# LM386.net
KiCad netlist of a schematic drawn in Altium Designer
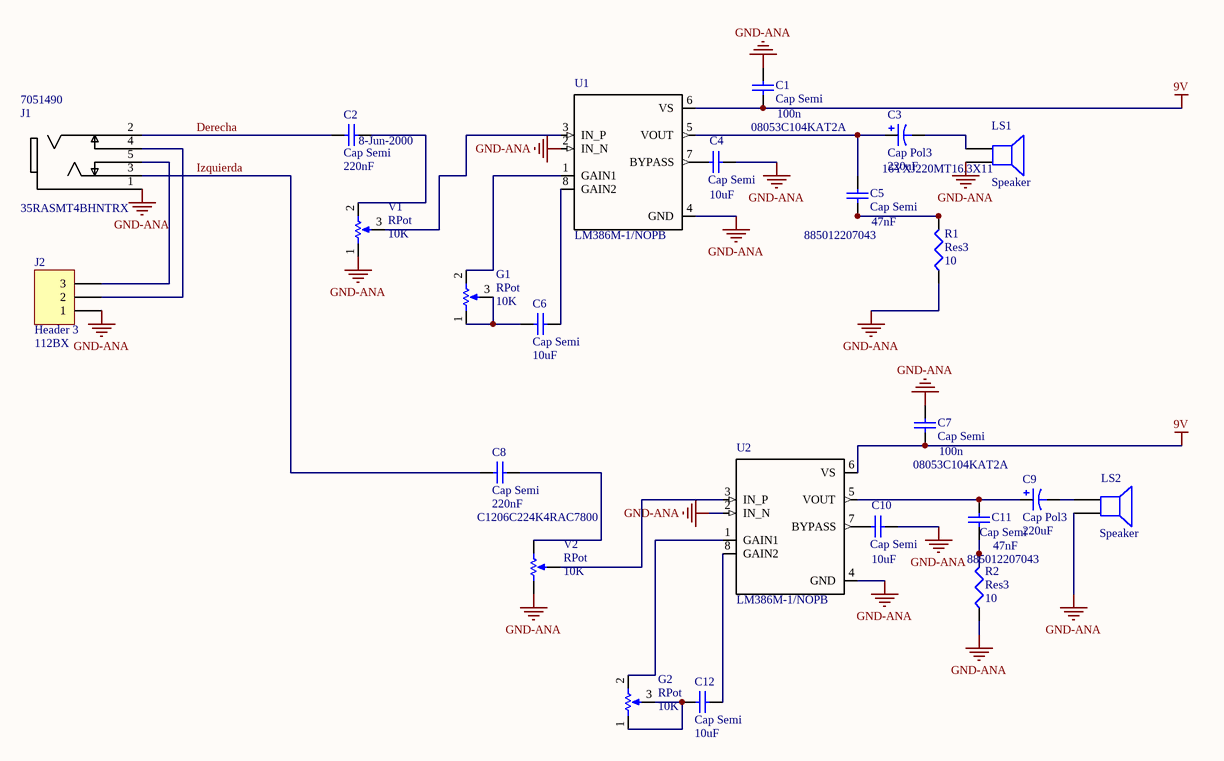
[diagram p0: LM386.SchDoc]

(export (version "E")
  (design (tool "Eeschema 10.0.6"))
  (components
    (comp (ref "C1")
      (value "Cap Semi")
      (footprint "C0805")
      (description "Capacitor (Semiconductor SIM Model)")
      (fields
        (field (name "ALTIUM_VALUE") "100n")
        (field (name "PN") "08053C104KAT2A")
        (field (name "PUBLISHER") "Altium Limited")
      )
      (libsource (lib "Miscellaneous Devices") (part "Cap Semi"))
    )
    (comp (ref "C2")
      (value "Cap Semi")
      (footprint "C1206")
      (description "Capacitor (Semiconductor SIM Model)")
      (fields
        (field (name "PUBLISHED") "8-Jun-2000")
        (field (name "ALTIUM_VALUE") "220nF")
        (field (name "PUBLISHER") "Altium Limited")
      )
      (libsource (lib "Miscellaneous Devices") (part "Cap Semi"))
    )
    (comp (ref "C3")
      (value "Cap Pol3")
      (footprint "C0805")
      (description "Polarized Capacitor (Surface Mount)")
      (fields
        (field (name "ALTIUM_VALUE") "220uF")
        (field (name "PN") "16YXJ220MT16.3X11")
        (field (name "PUBLISHER") "Altium Limited")
      )
      (libsource (lib "Miscellaneous Devices") (part "Cap Pol3"))
    )
    (comp (ref "C4")
      (value "Cap Semi")
      (footprint "C1206")
      (description "Capacitor (Semiconductor SIM Model)")
      (fields (field (name "ALTIUM_VALUE") "10uF") (field (name "PUBLISHER") "Altium Limited"))
      (libsource (lib "Miscellaneous Devices") (part "Cap Semi"))
    )
    (comp (ref "C5")
      (value "Cap Semi")
      (footprint "C0805")
      (description "Capacitor (Semiconductor SIM Model)")
      (fields
        (field (name "ALTIUM_VALUE") "47nF")
        (field (name "PN") "885012207043")
        (field (name "PUBLISHER") "Altium Limited")
      )
      (libsource (lib "Miscellaneous Devices") (part "Cap Semi"))
    )
    (comp (ref "C6")
      (value "Cap Semi")
      (footprint "C0805")
      (description "Capacitor (Semiconductor SIM Model)")
      (fields (field (name "ALTIUM_VALUE") "10uF") (field (name "PUBLISHER") "Altium Limited"))
      (libsource (lib "Miscellaneous Devices") (part "Cap Semi"))
    )
    (comp (ref "C7")
      (value "Cap Semi")
      (footprint "C0805")
      (description "Capacitor (Semiconductor SIM Model)")
      (fields
        (field (name "ALTIUM_VALUE") "100n")
        (field (name "PN") "08053C104KAT2A")
        (field (name "PUBLISHER") "Altium Limited")
      )
      (libsource (lib "Miscellaneous Devices") (part "Cap Semi"))
    )
    (comp (ref "C8")
      (value "Cap Semi")
      (footprint "C1206")
      (description "Capacitor (Semiconductor SIM Model)")
      (fields
        (field (name "ALTIUM_VALUE") "220nF")
        (field (name "PN") "C1206C224K4RAC7800")
        (field (name "PUBLISHER") "Altium Limited")
      )
      (libsource (lib "Miscellaneous Devices") (part "Cap Semi"))
    )
    (comp (ref "C9")
      (value "Cap Pol3")
      (footprint "C0805")
      (description "Polarized Capacitor (Surface Mount)")
      (fields (field (name "ALTIUM_VALUE") "220uF") (field (name "PUBLISHER") "Altium Limited"))
      (libsource (lib "Miscellaneous Devices") (part "Cap Pol3"))
    )
    (comp (ref "C10")
      (value "Cap Semi")
      (footprint "C0805")
      (description "Capacitor (Semiconductor SIM Model)")
      (fields (field (name "ALTIUM_VALUE") "10uF") (field (name "PUBLISHER") "Altium Limited"))
      (libsource (lib "Miscellaneous Devices") (part "Cap Semi"))
    )
    (comp (ref "C11")
      (value "Cap Semi")
      (footprint "C0805")
      (description "Capacitor (Semiconductor SIM Model)")
      (fields
        (field (name "ALTIUM_VALUE") "47nF")
        (field (name "PN") "885012207043")
        (field (name "PUBLISHER") "Altium Limited")
      )
      (libsource (lib "Miscellaneous Devices") (part "Cap Semi"))
    )
    (comp (ref "C12")
      (value "Cap Semi")
      (footprint "C0805")
      (description "Capacitor (Semiconductor SIM Model)")
      (fields (field (name "ALTIUM_VALUE") "10uF") (field (name "PUBLISHER") "Altium Limited"))
      (libsource (lib "Miscellaneous Devices") (part "Cap Semi"))
    )
    (comp (ref "G1")
      (value "RPot")
      (footprint "Potenciometer")
      (description "Potentiometer")
      (fields (field (name "ALTIUM_VALUE") "10K") (field (name "PUBLISHER") "Altium Limited"))
      (libsource (lib "Miscellaneous Devices") (part "RPot"))
    )
    (comp (ref "G2")
      (value "RPot")
      (footprint "Potenciometer")
      (description "Potentiometer")
      (fields (field (name "ALTIUM_VALUE") "10K") (field (name "PUBLISHER") "Altium Limited"))
      (libsource (lib "Miscellaneous Devices") (part "RPot"))
    )
    (comp (ref "J1")
      (value "35RASMT4BHNTRX")
      (footprint "SWITCHCRAFT_35RASMT4BHNTRX")
      (description "Conn 3.5MM Stereo Jack F 3 POS Solder RA SMD 5 Terminal 1 Port T/R")
      (fields (field (name "MF") "Switchcraft") (field (name "SUPPLIER PART NUMBER 1") "7051490"))
      (libsource (lib "35RASMT4BHNTRX") (part "35RASMT4BHNTRX"))
    )
    (comp (ref "J2")
      (value "Header 3")
      (footprint "HDR1X3")
      (description "Header, 3-Pin")
      (fields (field (name "PN") "112BX") (field (name "PUBLISHER") "Altium Limited"))
      (libsource (lib "Miscellaneous Connectors") (part "Header 3"))
    )
    (comp (ref "LS1")
      (value "Speaker")
      (footprint "PIN2")
      (description "Loudspeaker")
      (fields (field (name "PUBLISHER") "Altium Limited"))
      (libsource (lib "Miscellaneous Devices") (part "Speaker"))
    )
    (comp (ref "LS2")
      (value "Speaker")
      (footprint "PIN2")
      (description "Loudspeaker")
      (fields (field (name "PUBLISHER") "Altium Limited"))
      (libsource (lib "Miscellaneous Devices") (part "Speaker"))
    )
    (comp (ref "R1")
      (value "Res3")
      (footprint "SMD-0805-RES")
      (description "Resistor")
      (fields (field (name "ALTIUM_VALUE") "10") (field (name "PUBLISHER") "Altium Limited"))
      (libsource (lib "Miscellaneous Devices") (part "Res3"))
    )
    (comp (ref "R2")
      (value "Res3")
      (footprint "SMD-0805-RES")
      (description "Resistor")
      (fields (field (name "ALTIUM_VALUE") "10") (field (name "PUBLISHER") "Altium Limited"))
      (libsource (lib "Miscellaneous Devices") (part "Res3"))
    )
    (comp (ref "U1")
      (value "LM386M-1/NOPB")
      (footprint "SOIC127P600X175-8N")
      (description "Wide Input Voltage Low Power Audio Amplifier with Internal Gain 8-SOIC 0 to 70")
      (fields (field (name "MF") "Texas Instruments"))
      (libsource (lib "LM386M-1_NOPB") (part "LM386M-1/NOPB"))
    )
    (comp (ref "U2")
      (value "LM386M-1/NOPB")
      (footprint "SOIC127P600X175-8N")
      (description "Wide Input Voltage Low Power Audio Amplifier with Internal Gain 8-SOIC 0 to 70")
      (fields (field (name "MF") "Texas Instruments"))
      (libsource (lib "LM386M-1_NOPB") (part "LM386M-1/NOPB"))
    )
    (comp (ref "V1")
      (value "RPot")
      (footprint "Potenciometer")
      (description "Potentiometer")
      (fields (field (name "ALTIUM_VALUE") "10K") (field (name "PUBLISHER") "Altium Limited"))
      (libsource (lib "Miscellaneous Devices") (part "RPot"))
    )
    (comp (ref "V2")
      (value "RPot")
      (footprint "Potenciometer")
      (description "Potentiometer")
      (fields (field (name "ALTIUM_VALUE") "10K") (field (name "PUBLISHER") "Altium Limited"))
      (libsource (lib "") (part "RPot_1"))
    )
  )
  (nets
    (net (code "1") (name "/Derecha") (class "Default")
      (node (ref "C2") (pin "2") (pinfunction "2_2") (pintype "passive"))
      (node (ref "J1") (pin "2") (pinfunction "2_2") (pintype "passive"))
    )
    (net (code "2") (name "/Izquierda") (class "Default")
      (node (ref "C8") (pin "2") (pinfunction "2_2") (pintype "passive"))
      (node (ref "J1") (pin "3") (pinfunction "3_3") (pintype "passive"))
    )
    (net (code "3") (name "9V") (class "Default")
      (node (ref "C1") (pin "2") (pinfunction "2_2") (pintype "passive"))
      (node (ref "C7") (pin "2") (pinfunction "2_2") (pintype "passive"))
      (node (ref "U1") (pin "6") (pinfunction "VS_6") (pintype "power_in"))
      (node (ref "U2") (pin "6") (pinfunction "VS_6") (pintype "power_in"))
    )
    (net (code "4") (name "GND-ANA") (class "Default")
      (node (ref "C1") (pin "1") (pinfunction "1_1") (pintype "passive"))
      (node (ref "C10") (pin "1") (pinfunction "1_1") (pintype "passive"))
      (node (ref "C4") (pin "1") (pinfunction "1_1") (pintype "passive"))
      (node (ref "C7") (pin "1") (pinfunction "1_1") (pintype "passive"))
      (node (ref "J1") (pin "1") (pinfunction "1_1") (pintype "passive"))
      (node (ref "J2") (pin "1") (pinfunction "1_1") (pintype "passive"))
      (node (ref "LS1") (pin "2") (pinfunction "2_2") (pintype "passive"))
      (node (ref "LS2") (pin "2") (pinfunction "2_2") (pintype "passive"))
      (node (ref "R1") (pin "1") (pinfunction "1_1") (pintype "passive"))
      (node (ref "R2") (pin "1") (pinfunction "1_1") (pintype "passive"))
      (node (ref "U1") (pin "2") (pinfunction "IN_N_2") (pintype "input"))
      (node (ref "U1") (pin "4") (pinfunction "GND_4") (pintype "power_in"))
      (node (ref "U2") (pin "2") (pinfunction "IN_N_2") (pintype "input"))
      (node (ref "U2") (pin "4") (pinfunction "GND_4") (pintype "power_in"))
      (node (ref "V1") (pin "1") (pinfunction "TOP_1") (pintype "passive"))
      (node (ref "V2") (pin "1") (pinfunction "TOP_1") (pintype "passive"))
    )
    (net (code "5") (name "Net-(C3-Pad2)") (class "Default")
      (node (ref "C3") (pin "2") (pinfunction "2_2") (pintype "passive"))
      (node (ref "LS1") (pin "1") (pinfunction "1_1") (pintype "passive"))
    )
    (net (code "6") (name "Net-(C5-Pad2)") (class "Default")
      (node (ref "C5") (pin "2") (pinfunction "2_2") (pintype "passive"))
      (node (ref "R1") (pin "2") (pinfunction "2_2") (pintype "passive"))
    )
    (net (code "7") (name "Net-(C9-Pad2)") (class "Default")
      (node (ref "C9") (pin "2") (pinfunction "2_2") (pintype "passive"))
      (node (ref "LS2") (pin "1") (pinfunction "1_1") (pintype "passive"))
    )
    (net (code "8") (name "Net-(C11-Pad2)") (class "Default")
      (node (ref "C11") (pin "2") (pinfunction "2_2") (pintype "passive"))
      (node (ref "R2") (pin "2") (pinfunction "2_2") (pintype "passive"))
    )
    (net (code "9") (name "Net-(G1-BOT)") (class "Default")
      (node (ref "G1") (pin "2") (pinfunction "BOT_2") (pintype "passive"))
      (node (ref "U1") (pin "1") (pinfunction "GAIN1_1") (pintype "passive"))
    )
    (net (code "10") (name "Net-(G1-TAP)") (class "Default")
      (node (ref "C6") (pin "2") (pinfunction "2_2") (pintype "passive"))
      (node (ref "G1") (pin "1") (pinfunction "TOP_1") (pintype "passive"))
      (node (ref "G1") (pin "3") (pinfunction "TAP_3") (pintype "passive"))
    )
    (net (code "11") (name "Net-(G2-BOT)") (class "Default")
      (node (ref "G2") (pin "2") (pinfunction "BOT_2") (pintype "passive"))
      (node (ref "U2") (pin "1") (pinfunction "GAIN1_1") (pintype "passive"))
    )
    (net (code "12") (name "Net-(G2-TAP)") (class "Default")
      (node (ref "C12") (pin "2") (pinfunction "2_2") (pintype "passive"))
      (node (ref "G2") (pin "1") (pinfunction "TOP_1") (pintype "passive"))
      (node (ref "G2") (pin "3") (pinfunction "TAP_3") (pintype "passive"))
    )
    (net (code "13") (name "Net-(J1-Pad4)") (class "Default")
      (node (ref "J1") (pin "4") (pinfunction "4_4") (pintype "passive"))
      (node (ref "J2") (pin "2") (pinfunction "2_2") (pintype "passive"))
    )
    (net (code "14") (name "Net-(J1-Pad5)") (class "Default")
      (node (ref "J1") (pin "5") (pinfunction "5_5") (pintype "passive"))
      (node (ref "J2") (pin "3") (pinfunction "3_3") (pintype "passive"))
    )
    (net (code "15") (name "Net-(U1-BYPASS)") (class "Default")
      (node (ref "C4") (pin "2") (pinfunction "2_2") (pintype "passive"))
      (node (ref "U1") (pin "7") (pinfunction "BYPASS_7") (pintype "output"))
    )
    (net (code "16") (name "Net-(U1-GAIN2)") (class "Default")
      (node (ref "C6") (pin "1") (pinfunction "1_1") (pintype "passive"))
      (node (ref "U1") (pin "8") (pinfunction "GAIN2_8") (pintype "passive"))
    )
    (net (code "17") (name "Net-(U1-IN_P)") (class "Default")
      (node (ref "U1") (pin "3") (pinfunction "IN_P_3") (pintype "input"))
      (node (ref "V1") (pin "3") (pinfunction "TAP_3") (pintype "passive"))
    )
    (net (code "18") (name "Net-(U1-VOUT)") (class "Default")
      (node (ref "C3") (pin "1") (pinfunction "1_1") (pintype "passive"))
      (node (ref "C5") (pin "1") (pinfunction "1_1") (pintype "passive"))
      (node (ref "U1") (pin "5") (pinfunction "VOUT_5") (pintype "output"))
    )
    (net (code "19") (name "Net-(U2-BYPASS)") (class "Default")
      (node (ref "C10") (pin "2") (pinfunction "2_2") (pintype "passive"))
      (node (ref "U2") (pin "7") (pinfunction "BYPASS_7") (pintype "output"))
    )
    (net (code "20") (name "Net-(U2-GAIN2)") (class "Default")
      (node (ref "C12") (pin "1") (pinfunction "1_1") (pintype "passive"))
      (node (ref "U2") (pin "8") (pinfunction "GAIN2_8") (pintype "passive"))
    )
    (net (code "21") (name "Net-(U2-IN_P)") (class "Default")
      (node (ref "U2") (pin "3") (pinfunction "IN_P_3") (pintype "input"))
      (node (ref "V2") (pin "3") (pinfunction "TAP_3") (pintype "passive"))
    )
    (net (code "22") (name "Net-(U2-VOUT)") (class "Default")
      (node (ref "C11") (pin "1") (pinfunction "1_1") (pintype "passive"))
      (node (ref "C9") (pin "1") (pinfunction "1_1") (pintype "passive"))
      (node (ref "U2") (pin "5") (pinfunction "VOUT_5") (pintype "output"))
    )
    (net (code "23") (name "Net-(V1-BOT)") (class "Default")
      (node (ref "C2") (pin "1") (pinfunction "1_1") (pintype "passive"))
      (node (ref "V1") (pin "2") (pinfunction "BOT_2") (pintype "passive"))
    )
    (net (code "24") (name "Net-(V2-BOT)") (class "Default")
      (node (ref "C8") (pin "1") (pinfunction "1_1") (pintype "passive"))
      (node (ref "V2") (pin "2") (pinfunction "BOT_2") (pintype "passive"))
    )
  )
)
